# fish_tank.net
KiCad netlist of a schematic drawn in EAGLE
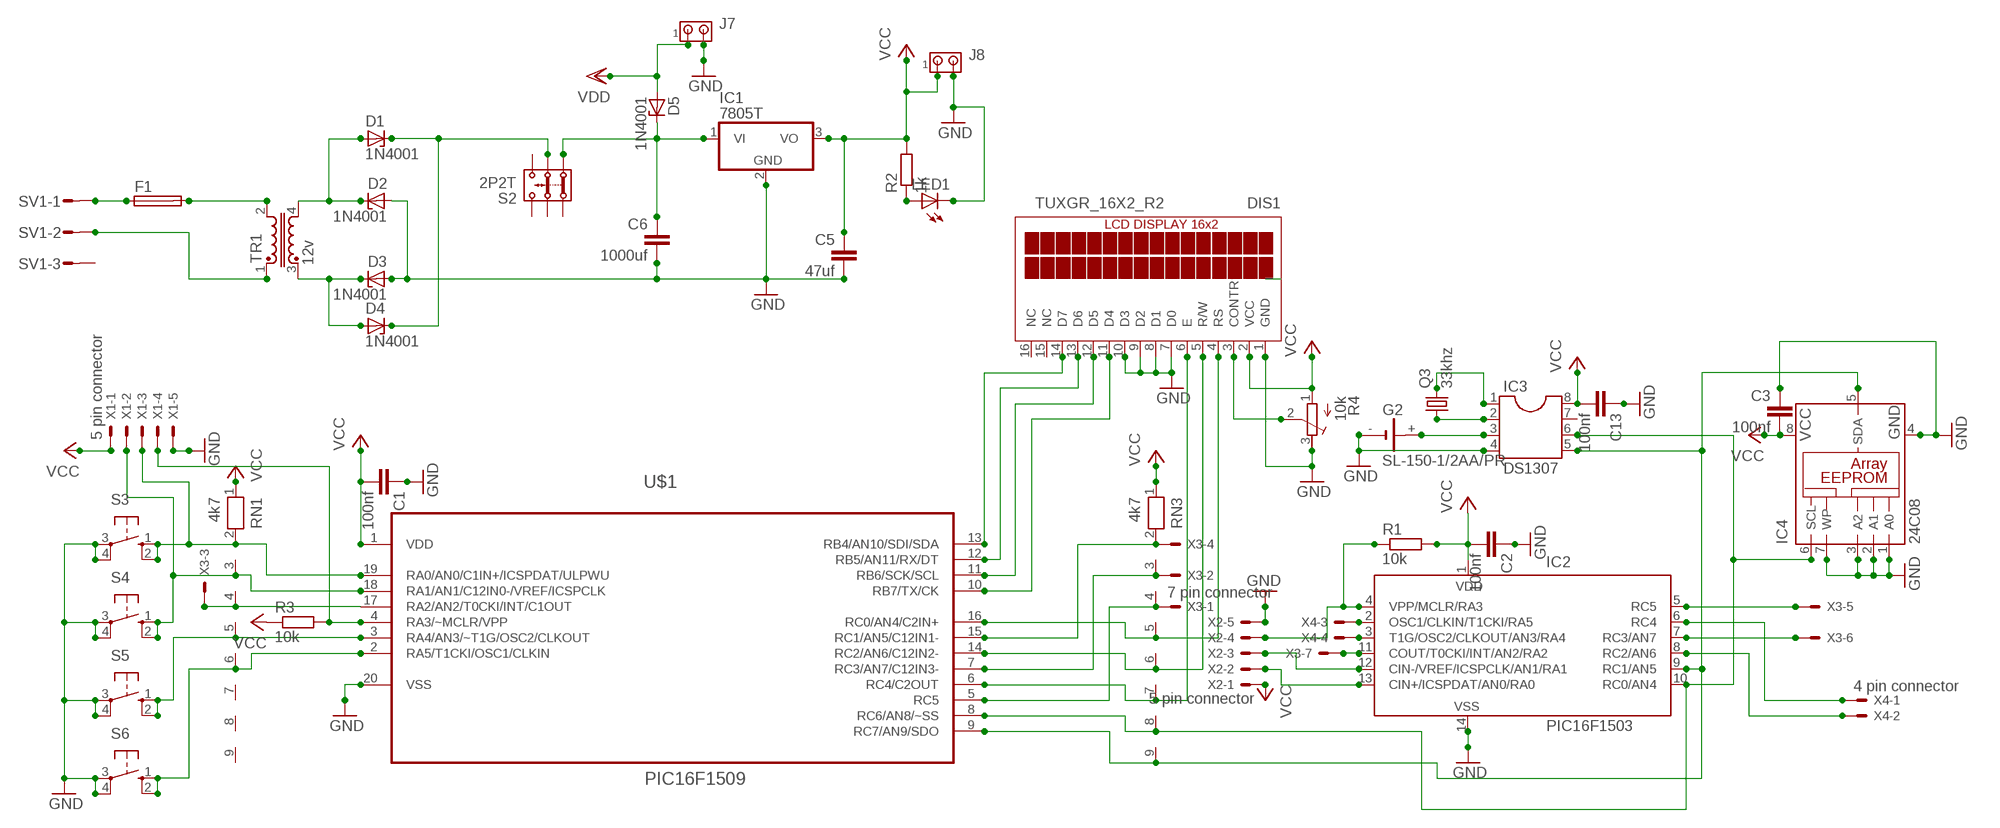
[diagram p0: schematic, sheet 1]

(export (version "E")
  (design (tool "Eeschema 10.0.6"))
  (components
    (comp (ref "C1")
      (value "100nf")
      (footprint "eagle-import:C2.5-4")
      (libsource (lib "eagle-import") (part "C2.5/4"))
    )
    (comp (ref "C2")
      (value "100nf")
      (footprint "eagle-import:C2.5-4")
      (libsource (lib "eagle-import") (part "C2.5/4"))
    )
    (comp (ref "C3")
      (value "100nf")
      (footprint "eagle-import:C5B2.5")
      (libsource (lib "eagle-import") (part "C5/2.5"))
    )
    (comp (ref "C5")
      (value "47uf")
      (footprint "eagle-import:C5B2.5")
      (libsource (lib "eagle-import") (part "C5/2.5"))
    )
    (comp (ref "C6")
      (value "1000uf")
      (footprint "eagle-import:C5B2.5")
      (libsource (lib "eagle-import") (part "C5/2.5"))
    )
    (comp (ref "C13")
      (value "100nf")
      (footprint "eagle-import:C5B2.5")
      (libsource (lib "eagle-import") (part "C5/2.5"))
    )
    (comp (ref "D1")
      (value "1N4001")
      (footprint "eagle-import:DO35Z10")
      (libsource (lib "eagle-import") (part "1N821"))
    )
    (comp (ref "D2")
      (value "1N4001")
      (footprint "eagle-import:DO35Z10")
      (libsource (lib "eagle-import") (part "1N821"))
    )
    (comp (ref "D3")
      (value "1N4001")
      (footprint "eagle-import:DO35Z10")
      (libsource (lib "eagle-import") (part "1N821"))
    )
    (comp (ref "D4")
      (value "1N4001")
      (footprint "eagle-import:DO35Z10")
      (libsource (lib "eagle-import") (part "1N821"))
    )
    (comp (ref "D5")
      (value "1N4001")
      (footprint "eagle-import:DO35Z10")
      (libsource (lib "eagle-import") (part "1N821"))
    )
    (comp (ref "DIS1")
      (value "TUXGR_16X2_R2")
      (footprint "eagle-import:TUXGR_16X2_R2")
      (libsource (lib "eagle-import") (part "TUXGR_16X2_R2"))
    )
    (comp (ref "F1")
      (value "SH25")
      (footprint "eagle-import:SH25")
      (fields (field (name "MF") "SCHURTER") (field (name "MPN") "0031.8211"))
      (libsource (lib "eagle-import") (part "SH25"))
    )
    (comp (ref "G2")
      (value "SL-150-1/2AA/PR")
      (footprint "eagle-import:SL-150-1_2AA_PR")
      (libsource (lib "eagle-import") (part "SL-150-1/2AA/PR"))
    )
    (comp (ref "IC1")
      (value "7805T")
      (footprint "eagle-import:TO220H")
      (libsource (lib "eagle-import") (part "78T05"))
    )
    (comp (ref "IC2")
      (value "PIC16F1503")
      (footprint "eagle-import:DIL14")
      (fields (field (name "MF") "MICROCHIP") (field (name "MPN") "PIC16F676-I/P"))
      (libsource (lib "eagle-import") (part "PIC16F676P"))
    )
    (comp (ref "IC3")
      (value "DS1307")
      (footprint "eagle-import:DIL08")
      (libsource (lib "eagle-import") (part "DIL8"))
    )
    (comp (ref "IC4")
      (value "24C08")
      (footprint "eagle-import:DIL8")
      (fields (field (name "MPN") "CAT24C04LI-G"))
      (libsource (lib "eagle-import") (part "24CP04C"))
    )
    (comp (ref "J7")
      (value "MTA02-100")
      (footprint "eagle-import:10X02MTA")
      (libsource (lib "eagle-import") (part "MTA02-100"))
    )
    (comp (ref "J8")
      (value "MTA02-100")
      (footprint "eagle-import:10X02MTA")
      (libsource (lib "eagle-import") (part "MTA02-100"))
    )
    (comp (ref "LED1")
      (value "LED3MM")
      (footprint "eagle-import:LED3MM")
      (libsource (lib "eagle-import") (part "LED3MM"))
    )
    (comp (ref "Q3")
      (value "33khz")
      (footprint "eagle-import:TC26H")
      (libsource (lib "eagle-import") (part "CRYSTALTC26H"))
    )
    (comp (ref "R1")
      (value "10k")
      (footprint "eagle-import:0207_7")
      (libsource (lib "eagle-import") (part "R-EU_0207/7"))
    )
    (comp (ref "R2")
      (value "1k")
      (footprint "eagle-import:0204_5")
      (libsource (lib "eagle-import") (part "resistor_R-EU_0204/5"))
    )
    (comp (ref "R3")
      (value "10k")
      (footprint "eagle-import:0207_7")
      (libsource (lib "eagle-import") (part "R-EU_0207/7"))
    )
    (comp (ref "R4")
      (value "10k")
      (footprint "eagle-import:RTRIM64W")
      (libsource (lib "eagle-import") (part "R-TRIMM64W"))
    )
    (comp (ref "RN1")
      (value "4k7")
      (footprint "eagle-import:RN-9")
      (libsource (lib "eagle-import") (part "RN08"))
    )
    (comp (ref "RN3")
      (value "4k7")
      (footprint "eagle-import:RN-9")
      (libsource (lib "eagle-import") (part "RN08"))
    )
    (comp (ref "S2")
      (value "2P2T")
      (footprint "eagle-import:2P2T")
      (libsource (lib "eagle-import") (part "2P2T"))
    )
    (comp (ref "S3")
      (value "10-XX")
      (footprint "eagle-import:B3F-10XX")
      (fields (field (name "MPN") "B3F-1000"))
      (libsource (lib "eagle-import") (part "10-XX"))
    )
    (comp (ref "S4")
      (value "10-XX")
      (footprint "eagle-import:B3F-10XX")
      (fields (field (name "MPN") "B3F-1000"))
      (libsource (lib "eagle-import") (part "10-XX"))
    )
    (comp (ref "S5")
      (value "10-XX")
      (footprint "eagle-import:B3F-10XX")
      (fields (field (name "MPN") "B3F-1000"))
      (libsource (lib "eagle-import") (part "10-XX"))
    )
    (comp (ref "S6")
      (value "10-XX")
      (footprint "eagle-import:B3F-10XX")
      (fields (field (name "MPN") "B3F-1000"))
      (libsource (lib "eagle-import") (part "10-XX"))
    )
    (comp (ref "SV1")
      (value "MT6-3Y")
      (footprint "eagle-import:MT6-3Y")
      (libsource (lib "eagle-import") (part "MT6-3Y"))
    )
    (comp (ref "TR1")
      (value "12v")
      (footprint "eagle-import:U15")
      (libsource (lib "eagle-import") (part "U15-TRANSFORMER"))
    )
    (comp (ref "U$1")
      (value "PIC16F1509")
      (footprint "eagle-import:DIP254P762X533-20")
      (fields (field (name "MPN") "PIC16F689-I/P"))
      (libsource (lib "eagle-import") (part "PIC16F689-I/P"))
    )
    (comp (ref "X1")
      (value "5 pin connector")
      (footprint "eagle-import:22-23-2051")
      (fields (field (name "MF") "MOLEX") (field (name "MPN") "22-23-2051"))
      (libsource (lib "eagle-import") (part "22-23-2051"))
    )
    (comp (ref "X2")
      (value "5 pin connector")
      (footprint "eagle-import:22-23-2051")
      (fields (field (name "MF") "MOLEX") (field (name "MPN") "22-23-2051"))
      (libsource (lib "eagle-import") (part "22-23-2051"))
    )
    (comp (ref "X3")
      (value "7 pin connector")
      (footprint "eagle-import:22-23-2071")
      (fields (field (name "MF") "MOLEX") (field (name "MPN") "22-23-2071"))
      (libsource (lib "eagle-import") (part "22-23-2071"))
    )
    (comp (ref "X4")
      (value "4 pin connector")
      (footprint "eagle-import:22-23-2041")
      (fields (field (name "MF") "MOLEX") (field (name "MPN") "22-23-2041"))
      (libsource (lib "eagle-import") (part "22-23-2041"))
    )
  )
  (nets
    (net (code "1") (name "GND") (class "Default")
      (node (ref "C1") (pin "1") (pinfunction "1_1") (pintype "passive"))
      (node (ref "C13") (pin "1") (pinfunction "1_1") (pintype "passive"))
      (node (ref "C2") (pin "1") (pinfunction "1_1") (pintype "passive"))
      (node (ref "C3") (pin "1") (pinfunction "1_1") (pintype "passive"))
      (node (ref "C5") (pin "2") (pinfunction "2_2") (pintype "passive"))
      (node (ref "C6") (pin "2") (pinfunction "2_2") (pintype "passive"))
      (node (ref "D2") (pin "A") (pinfunction "A_A") (pintype "passive"))
      (node (ref "D3") (pin "A") (pinfunction "A_A") (pintype "passive"))
      (node (ref "DIS1") (pin "1") (pinfunction "GND_1") (pintype "power_in"))
      (node (ref "DIS1") (pin "10") (pinfunction "D3_10") (pintype "input"))
      (node (ref "DIS1") (pin "7") (pinfunction "D0_7") (pintype "input"))
      (node (ref "DIS1") (pin "8") (pinfunction "D1_8") (pintype "input"))
      (node (ref "DIS1") (pin "9") (pinfunction "D2_9") (pintype "input"))
      (node (ref "G2") (pin "-") (pinfunction "-_-") (pintype "passive"))
      (node (ref "IC1") (pin "2") (pinfunction "GND_2") (pintype "passive"))
      (node (ref "IC2") (pin "14") (pinfunction "VSS_14") (pintype "power_in"))
      (node (ref "IC3") (pin "4") (pinfunction "4_4") (pintype "passive"))
      (node (ref "IC4") (pin "1") (pinfunction "A0_1") (pintype "input"))
      (node (ref "IC4") (pin "2") (pinfunction "A1_2") (pintype "input"))
      (node (ref "IC4") (pin "3") (pinfunction "A2_3") (pintype "input"))
      (node (ref "IC4") (pin "4") (pinfunction "GND_4") (pintype "power_in"))
      (node (ref "IC4") (pin "7") (pinfunction "WP_7") (pintype "input"))
      (node (ref "J7") (pin "2") (pinfunction "2_2") (pintype "passive"))
      (node (ref "J8") (pin "2") (pinfunction "2_2") (pintype "passive"))
      (node (ref "LED1") (pin "K") (pinfunction "C_K") (pintype "passive"))
      (node (ref "R4") (pin "3") (pinfunction "E_3") (pintype "passive"))
      (node (ref "S3") (pin "3") (pinfunction "P_3") (pintype "passive"))
      (node (ref "S3") (pin "4") (pinfunction "P1_4") (pintype "passive"))
      (node (ref "S4") (pin "3") (pinfunction "P_3") (pintype "passive"))
      (node (ref "S4") (pin "4") (pinfunction "P1_4") (pintype "passive"))
      (node (ref "S5") (pin "3") (pinfunction "P_3") (pintype "passive"))
      (node (ref "S5") (pin "4") (pinfunction "P1_4") (pintype "passive"))
      (node (ref "S6") (pin "3") (pinfunction "P_3") (pintype "passive"))
      (node (ref "S6") (pin "4") (pinfunction "P1_4") (pintype "passive"))
      (node (ref "U$1") (pin "20") (pinfunction "VSS_20") (pintype "power_in"))
      (node (ref "X1") (pin "5") (pinfunction "S_5") (pintype "passive"))
      (node (ref "X2") (pin "5") (pinfunction "S_5") (pintype "passive"))
    )
    (net (code "2") (name "Net-(D1-PadA)") (class "Default")
      (node (ref "D1") (pin "A") (pinfunction "A_A") (pintype "passive"))
      (node (ref "D2") (pin "C") (pinfunction "C_C") (pintype "passive"))
      (node (ref "TR1") (pin "4") (pinfunction "4_4") (pintype "passive"))
    )
    (net (code "3") (name "Net-(D1-PadC)") (class "Default")
      (node (ref "D1") (pin "C") (pinfunction "C_C") (pintype "passive"))
      (node (ref "D4") (pin "C") (pinfunction "C_C") (pintype "passive"))
      (node (ref "S2") (pin "2.2") (pinfunction "2.2_2.2") (pintype "passive"))
    )
    (net (code "4") (name "Net-(D3-PadC)") (class "Default")
      (node (ref "D3") (pin "C") (pinfunction "C_C") (pintype "passive"))
      (node (ref "D4") (pin "A") (pinfunction "A_A") (pintype "passive"))
      (node (ref "TR1") (pin "3") (pinfunction "3_3") (pintype "passive"))
    )
    (net (code "5") (name "Net-(DIS1-CONTR)") (class "Default")
      (node (ref "DIS1") (pin "3") (pinfunction "CONTR_3") (pintype "input"))
      (node (ref "R4") (pin "2") (pinfunction "S_2") (pintype "passive"))
    )
    (net (code "6") (name "Net-(DIS1-D4)") (class "Default")
      (node (ref "DIS1") (pin "11") (pinfunction "D4_11") (pintype "input"))
      (node (ref "U$1") (pin "10") (pinfunction "RB7/TX/CK_10") (pintype "bidirectional"))
    )
    (net (code "7") (name "Net-(DIS1-D5)") (class "Default")
      (node (ref "DIS1") (pin "12") (pinfunction "D5_12") (pintype "input"))
      (node (ref "U$1") (pin "11") (pinfunction "RB6/SCK/SCL_11") (pintype "bidirectional"))
    )
    (net (code "8") (name "Net-(DIS1-D6)") (class "Default")
      (node (ref "DIS1") (pin "13") (pinfunction "D6_13") (pintype "input"))
      (node (ref "U$1") (pin "12") (pinfunction "RB5/AN11/RX/DT_12") (pintype "bidirectional"))
    )
    (net (code "9") (name "Net-(DIS1-D7)") (class "Default")
      (node (ref "DIS1") (pin "14") (pinfunction "D7_14") (pintype "input"))
      (node (ref "U$1") (pin "13") (pinfunction "RB4/AN10/SDI/SDA_13") (pintype "bidirectional"))
    )
    (net (code "10") (name "Net-(DIS1-E)") (class "Default")
      (node (ref "DIS1") (pin "6") (pinfunction "E_6") (pintype "input"))
      (node (ref "RN3") (pin "7") (pinfunction "7_7") (pintype "passive"))
      (node (ref "U$1") (pin "6") (pinfunction "RC4/C2OUT_6") (pintype "bidirectional"))
    )
    (net (code "11") (name "Net-(DIS1-RS)") (class "Default")
      (node (ref "DIS1") (pin "4") (pinfunction "RS_4") (pintype "input"))
      (node (ref "RN3") (pin "5") (pinfunction "5_5") (pintype "passive"))
      (node (ref "U$1") (pin "16") (pinfunction "RC0/AN4/C2IN+_16") (pintype "bidirectional"))
    )
    (net (code "12") (name "Net-(DIS1-R{slash}W)") (class "Default")
      (node (ref "DIS1") (pin "5") (pinfunction "R/W_5") (pintype "input"))
      (node (ref "RN3") (pin "6") (pinfunction "6_6") (pintype "passive"))
      (node (ref "U$1") (pin "14") (pinfunction "RC2/AN6/C12IN2-_14") (pintype "bidirectional"))
    )
    (net (code "13") (name "Net-(F1-Pad2)") (class "Default")
      (node (ref "F1") (pin "2") (pinfunction "2_2") (pintype "passive"))
      (node (ref "TR1") (pin "2") (pinfunction "2_2") (pintype "passive"))
    )
    (net (code "14") (name "Net-(G2-Pad+)") (class "Default")
      (node (ref "G2") (pin "+") (pinfunction "+_+") (pintype "passive"))
      (node (ref "IC3") (pin "3") (pinfunction "3_3") (pintype "passive"))
    )
    (net (code "15") (name "Net-(IC1-VI)") (class "Default")
      (node (ref "C6") (pin "1") (pinfunction "1_1") (pintype "passive"))
      (node (ref "D5") (pin "C") (pinfunction "C_C") (pintype "passive"))
      (node (ref "IC1") (pin "1") (pinfunction "VI_1") (pintype "input"))
      (node (ref "S2") (pin "1.2") (pinfunction "1.2_1.2") (pintype "passive"))
    )
    (net (code "16") (name "Net-(IC2-CIN+{slash}ICSPDAT{slash}AN0{slash}RA0)") (class "Default")
      (node (ref "IC2") (pin "13") (pinfunction "CIN+/ICSPDAT/AN0/RA0_13") (pintype "bidirectional"))
      (node (ref "X2") (pin "2") (pinfunction "S_2") (pintype "passive"))
    )
    (net (code "17") (name "Net-(IC2-CIN-{slash}VREF{slash}ICSPCLK{slash}AN1{slash}RA1)") (class "Default")
      (node (ref "IC2") (pin "12") (pinfunction "CIN-/VREF/ICSPCLK/AN1/RA1_12") (pintype "bidirectional"))
      (node (ref "X2") (pin "3") (pinfunction "S_3") (pintype "passive"))
    )
    (net (code "18") (name "Net-(IC2-COUT{slash}T0CKI{slash}INT{slash}AN2{slash}RA2)") (class "Default")
      (node (ref "IC2") (pin "11") (pinfunction "COUT/T0CKI/INT/AN2/RA2_11") (pintype "bidirectional"))
      (node (ref "X3") (pin "7") (pinfunction "S_7") (pintype "passive"))
    )
    (net (code "19") (name "Net-(IC2-OSC1{slash}CLKIN{slash}T1CKI{slash}RA5)") (class "Default")
      (node (ref "IC2") (pin "2") (pinfunction "OSC1/CLKIN/T1CKI/RA5_2") (pintype "bidirectional"))
      (node (ref "X4") (pin "3") (pinfunction "S_3") (pintype "passive"))
    )
    (net (code "20") (name "Net-(IC2-RC0{slash}AN4)") (class "Default")
      (node (ref "IC2") (pin "10") (pinfunction "RC0/AN4_10") (pintype "bidirectional"))
      (node (ref "IC3") (pin "6") (pinfunction "6_6") (pintype "passive"))
      (node (ref "IC4") (pin "6") (pinfunction "SCL_6") (pintype "input"))
      (node (ref "RN3") (pin "8") (pinfunction "8_8") (pintype "passive"))
      (node (ref "U$1") (pin "8") (pinfunction "RC6/AN8/~{SS}_8") (pintype "bidirectional"))
    )
    (net (code "21") (name "Net-(IC2-RC1{slash}AN5)") (class "Default")
      (node (ref "IC2") (pin "9") (pinfunction "RC1/AN5_9") (pintype "bidirectional"))
      (node (ref "IC3") (pin "5") (pinfunction "5_5") (pintype "passive"))
      (node (ref "IC4") (pin "5") (pinfunction "SDA_5") (pintype "bidirectional"))
      (node (ref "RN3") (pin "9") (pinfunction "9_9") (pintype "passive"))
      (node (ref "U$1") (pin "9") (pinfunction "RC7/AN9/SDO_9") (pintype "bidirectional"))
    )
    (net (code "22") (name "Net-(IC2-RC2{slash}AN6)") (class "Default")
      (node (ref "IC2") (pin "8") (pinfunction "RC2/AN6_8") (pintype "bidirectional"))
      (node (ref "X4") (pin "2") (pinfunction "S_2") (pintype "passive"))
    )
    (net (code "23") (name "Net-(IC2-RC3{slash}AN7)") (class "Default")
      (node (ref "IC2") (pin "7") (pinfunction "RC3/AN7_7") (pintype "bidirectional"))
      (node (ref "X3") (pin "6") (pinfunction "S_6") (pintype "passive"))
    )
    (net (code "24") (name "Net-(IC2-RC4)") (class "Default")
      (node (ref "IC2") (pin "6") (pinfunction "RC4_6") (pintype "bidirectional"))
      (node (ref "X4") (pin "1") (pinfunction "S_1") (pintype "passive"))
    )
    (net (code "25") (name "Net-(IC2-RC5)") (class "Default")
      (node (ref "IC2") (pin "5") (pinfunction "RC5_5") (pintype "bidirectional"))
      (node (ref "X3") (pin "5") (pinfunction "S_5") (pintype "passive"))
    )
    (net (code "26") (name "Net-(IC2-T1G{slash}OSC2{slash}CLKOUT{slash}AN3{slash}RA4)") (class "Default")
      (node (ref "IC2") (pin "3") (pinfunction "T1G/OSC2/CLKOUT/AN3/RA4_3") (pintype "bidirectional"))
      (node (ref "X4") (pin "4") (pinfunction "S_4") (pintype "passive"))
    )
    (net (code "27") (name "Net-(IC2-VPP{slash}MCLR{slash}RA3)") (class "Default")
      (node (ref "IC2") (pin "4") (pinfunction "VPP/MCLR/RA3_4") (pintype "input"))
      (node (ref "R1") (pin "1") (pinfunction "1_1") (pintype "passive"))
      (node (ref "X2") (pin "4") (pinfunction "S_4") (pintype "passive"))
    )
    (net (code "28") (name "Net-(IC3-Pad1)") (class "Default")
      (node (ref "IC3") (pin "1") (pinfunction "1_1") (pintype "passive"))
      (node (ref "Q3") (pin "2") (pinfunction "2_2") (pintype "passive"))
    )
    (net (code "29") (name "Net-(IC3-Pad2)") (class "Default")
      (node (ref "IC3") (pin "2") (pinfunction "2_2") (pintype "passive"))
      (node (ref "Q3") (pin "1") (pinfunction "1_1") (pintype "passive"))
    )
    (net (code "30") (name "Net-(LED1-PadA)") (class "Default")
      (node (ref "LED1") (pin "A") (pinfunction "A_A") (pintype "passive"))
      (node (ref "R2") (pin "1") (pinfunction "1_1") (pintype "passive"))
    )
    (net (code "31") (name "Net-(S3-S)") (class "Default")
      (node (ref "RN1") (pin "2") (pinfunction "2_2") (pintype "passive"))
      (node (ref "S3") (pin "1") (pinfunction "S_1") (pintype "passive"))
      (node (ref "S3") (pin "2") (pinfunction "S1_2") (pintype "passive"))
      (node (ref "U$1") (pin "19") (pinfunction "RA0/AN0/C1IN+/ICSPDAT/ULPWU_19") (pintype "bidirectional"))
      (node (ref "X1") (pin "3") (pinfunction "S_3") (pintype "passive"))
    )
    (net (code "32") (name "Net-(S4-S)") (class "Default")
      (node (ref "RN1") (pin "3") (pinfunction "3_3") (pintype "passive"))
      (node (ref "S4") (pin "1") (pinfunction "S_1") (pintype "passive"))
      (node (ref "S4") (pin "2") (pinfunction "S1_2") (pintype "passive"))
      (node (ref "U$1") (pin "18") (pinfunction "RA1/AN1/C12IN0-/VREF/ICSPCLK_18") (pintype "bidirectional"))
      (node (ref "X1") (pin "2") (pinfunction "S_2") (pintype "passive"))
    )
    (net (code "33") (name "Net-(S5-S)") (class "Default")
      (node (ref "RN1") (pin "5") (pinfunction "5_5") (pintype "passive"))
      (node (ref "S5") (pin "1") (pinfunction "S_1") (pintype "passive"))
      (node (ref "S5") (pin "2") (pinfunction "S1_2") (pintype "passive"))
      (node (ref "U$1") (pin "3") (pinfunction "RA4/AN3/~{T1G/OSC2/CLKOUT}_3") (pintype "bidirectional"))
    )
    (net (code "34") (name "Net-(S6-S)") (class "Default")
      (node (ref "RN1") (pin "6") (pinfunction "6_6") (pintype "passive"))
      (node (ref "S6") (pin "1") (pinfunction "S_1") (pintype "passive"))
      (node (ref "S6") (pin "2") (pinfunction "S1_2") (pintype "passive"))
      (node (ref "U$1") (pin "2") (pinfunction "RA5/T1CKI/OSC1/CLKIN_2") (pintype "bidirectional"))
    )
    (net (code "35") (name "Net-(SV1A-S)") (class "Default")
      (node (ref "F1") (pin "1") (pinfunction "1_1") (pintype "passive"))
      (node (ref "SV1") (pin "1") (pinfunction "S_1") (pintype "passive"))
    )
    (net (code "36") (name "Net-(SV1B-S)") (class "Default")
      (node (ref "SV1") (pin "2") (pinfunction "S_2") (pintype "passive"))
      (node (ref "TR1") (pin "1") (pinfunction "1_1") (pintype "passive"))
    )
    (net (code "37") (name "Net-(U$1-RA2{slash}AN2{slash}T0CKI{slash}INT{slash}C1OUT)") (class "Default")
      (node (ref "RN1") (pin "4") (pinfunction "4_4") (pintype "passive"))
      (node (ref "U$1") (pin "17") (pinfunction "RA2/AN2/T0CKI/INT/C1OUT_17") (pintype "bidirectional"))
      (node (ref "X3") (pin "3") (pinfunction "S_3") (pintype "passive"))
    )
    (net (code "38") (name "Net-(U$1-RA3{slash}~{MCLR{slash}VPP})") (class "Default")
      (node (ref "R3") (pin "2") (pinfunction "2_2") (pintype "passive"))
      (node (ref "U$1") (pin "4") (pinfunction "RA3/~{MCLR/VPP}_4") (pintype "input"))
      (node (ref "X1") (pin "4") (pinfunction "S_4") (pintype "passive"))
    )
    (net (code "39") (name "Net-(U$1-RC1{slash}AN5{slash}C12IN1-)") (class "Default")
      (node (ref "RN3") (pin "2") (pinfunction "2_2") (pintype "passive"))
      (node (ref "U$1") (pin "15") (pinfunction "RC1/AN5/C12IN1-_15") (pintype "bidirectional"))
      (node (ref "X3") (pin "4") (pinfunction "S_4") (pintype "passive"))
    )
    (net (code "40") (name "Net-(U$1-RC3{slash}AN7{slash}C12IN3-)") (class "Default")
      (node (ref "RN3") (pin "3") (pinfunction "3_3") (pintype "passive"))
      (node (ref "U$1") (pin "7") (pinfunction "RC3/AN7/C12IN3-_7") (pintype "bidirectional"))
      (node (ref "X3") (pin "2") (pinfunction "S_2") (pintype "passive"))
    )
    (net (code "41") (name "Net-(U$1-RC5)") (class "Default")
      (node (ref "RN3") (pin "4") (pinfunction "4_4") (pintype "passive"))
      (node (ref "U$1") (pin "5") (pinfunction "RC5_5") (pintype "bidirectional"))
      (node (ref "X3") (pin "1") (pinfunction "S_1") (pintype "passive"))
    )
    (net (code "42") (name "VCC") (class "Default")
      (node (ref "C1") (pin "2") (pinfunction "2_2") (pintype "passive"))
      (node (ref "C13") (pin "2") (pinfunction "2_2") (pintype "passive"))
      (node (ref "C2") (pin "2") (pinfunction "2_2") (pintype "passive"))
      (node (ref "C3") (pin "2") (pinfunction "2_2") (pintype "passive"))
      (node (ref "C5") (pin "1") (pinfunction "1_1") (pintype "passive"))
      (node (ref "DIS1") (pin "2") (pinfunction "VCC_2") (pintype "power_in"))
      (node (ref "IC1") (pin "3") (pinfunction "VO_3") (pintype "passive"))
      (node (ref "IC2") (pin "1") (pinfunction "VDD_1") (pintype "power_in"))
      (node (ref "IC3") (pin "8") (pinfunction "8_8") (pintype "passive"))
      (node (ref "IC4") (pin "8") (pinfunction "VCC_8") (pintype "power_in"))
      (node (ref "J8") (pin "1") (pinfunction "1_1") (pintype "passive"))
      (node (ref "R1") (pin "2") (pinfunction "2_2") (pintype "passive"))
      (node (ref "R2") (pin "2") (pinfunction "2_2") (pintype "passive"))
      (node (ref "R3") (pin "1") (pinfunction "1_1") (pintype "passive"))
      (node (ref "R4") (pin "1") (pinfunction "A_1") (pintype "passive"))
      (node (ref "RN1") (pin "1") (pinfunction "1_1") (pintype "passive"))
      (node (ref "RN3") (pin "1") (pinfunction "1_1") (pintype "passive"))
      (node (ref "U$1") (pin "1") (pinfunction "VDD_1") (pintype "power_in"))
      (node (ref "X1") (pin "1") (pinfunction "S_1") (pintype "passive"))
      (node (ref "X2") (pin "1") (pinfunction "S_1") (pintype "passive"))
    )
    (net (code "43") (name "VDD") (class "Default")
      (node (ref "D5") (pin "A") (pinfunction "A_A") (pintype "passive"))
      (node (ref "J7") (pin "1") (pinfunction "1_1") (pintype "passive"))
    )
    (net (code "44") (name "unconnected-(DIS1-NC-Pad15)") (class "Default")
      (node (ref "DIS1") (pin "15") (pinfunction "NC_15") (pintype "no_connect"))
    )
    (net (code "45") (name "unconnected-(DIS1-NC-Pad16)") (class "Default")
      (node (ref "DIS1") (pin "16") (pinfunction "NC_16") (pintype "no_connect"))
    )
    (net (code "46") (name "unconnected-(IC3-Pad7)") (class "Default")
      (node (ref "IC3") (pin "7") (pinfunction "7_7") (pintype "passive"))
    )
    (net (code "47") (name "unconnected-(RN1-Pad7)") (class "Default")
      (node (ref "RN1") (pin "7") (pinfunction "7_7") (pintype "passive"))
    )
    (net (code "48") (name "unconnected-(RN1-Pad8)") (class "Default")
      (node (ref "RN1") (pin "8") (pinfunction "8_8") (pintype "passive"))
    )
    (net (code "49") (name "unconnected-(RN1-Pad9)") (class "Default")
      (node (ref "RN1") (pin "9") (pinfunction "9_9") (pintype "passive"))
    )
    (net (code "50") (name "unconnected-(S2-Pad1.1)") (class "Default")
      (node (ref "S2") (pin "1.1") (pinfunction "1.1_1.1") (pintype "passive"))
    )
    (net (code "51") (name "unconnected-(S2-Pad2.1)") (class "Default")
      (node (ref "S2") (pin "2.1") (pinfunction "2.1_2.1") (pintype "passive"))
    )
    (net (code "52") (name "unconnected-(S2-Pad3.1)") (class "Default")
      (node (ref "S2") (pin "3.1") (pinfunction "3.1_3.1") (pintype "passive"))
    )
    (net (code "53") (name "unconnected-(S2-Pad3.2)") (class "Default")
      (node (ref "S2") (pin "3.2") (pinfunction "3.2_3.2") (pintype "passive"))
    )
    (net (code "54") (name "unconnected-(SV1C-S-Pad3)") (class "Default")
      (node (ref "SV1") (pin "3") (pinfunction "S_3") (pintype "passive"))
    )
  )
)
